# QUAD_BUCK.net
KiCad netlist of a schematic drawn in Altium Designer
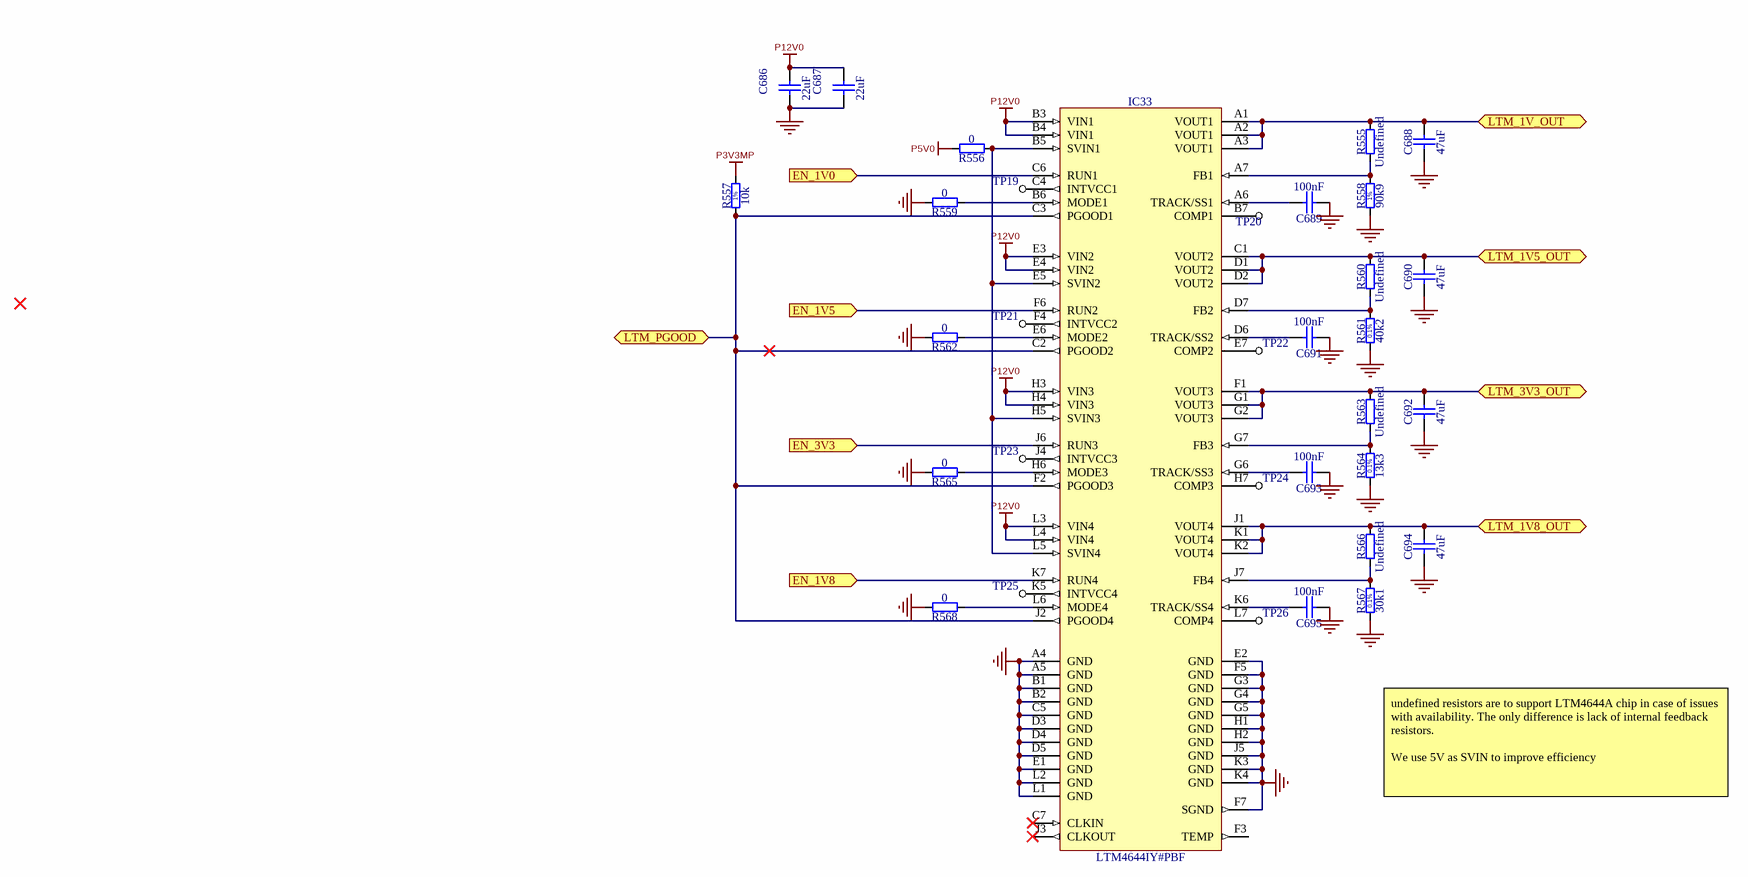
[diagram p0: QUAD_BUCK.SchDoc]

(export (version "E")
  (design (tool "Eeschema 10.0.6"))
  (components
    (comp (ref "C686")
      (value "22uF")
      (footprint "CAPC2012X135N")
      (description "Non-polarised capacitor")
      (fields
        (field (name "MANUFACTURER PART NUMBER") "CC0805_22UF_16V_10%_X5R")
        (field (name "MANUFACTURER") "GENERIC")
        (field (name "AUTHOR") "CERN DEM JLC")
      )
      (libsource (lib "Capacitors") (part "Capacitor - non polarized"))
    )
    (comp (ref "C687")
      (value "22uF")
      (footprint "CAPC2012X135N")
      (description "Non-polarised capacitor")
      (fields
        (field (name "MANUFACTURER PART NUMBER") "CC0805_22UF_16V_10%_X5R")
        (field (name "MANUFACTURER") "GENERIC")
        (field (name "AUTHOR") "CERN DEM JLC")
      )
      (libsource (lib "Capacitors") (part "Capacitor - non polarized"))
    )
    (comp (ref "C688")
      (value "47uF")
      (footprint "CAPC2012X140N")
      (description "Non-polarised capacitor")
      (fields
        (field (name "MANUFACTURER PART NUMBER") "CC0805_47UF_6.3V_20%_X5R")
        (field (name "MANUFACTURER") "GENERIC")
        (field (name "AUTHOR") "CERN DEM JLC")
      )
      (libsource (lib "Capacitors") (part "Capacitor - non polarized"))
    )
    (comp (ref "C689")
      (value "100nF")
      (footprint "CAPC1005X55N")
      (description "Non-polarised capacitor")
      (fields
        (field (name "PART NUMBER") "CC0402_100NF_16V_10%_X5R")
        (field (name "VOLTAGE") "16V")
        (field (name "AUTHOR") "CERN DEM JLC")
      )
      (libsource (lib "Capacitors") (part "Capacitor - non polarized"))
    )
    (comp (ref "C690")
      (value "47uF")
      (footprint "CAPC2012X140N")
      (description "Non-polarised capacitor")
      (fields
        (field (name "MANUFACTURER PART NUMBER") "CC0805_47UF_6.3V_20%_X5R")
        (field (name "MANUFACTURER") "GENERIC")
        (field (name "AUTHOR") "CERN DEM JLC")
      )
      (libsource (lib "Capacitors") (part "Capacitor - non polarized"))
    )
    (comp (ref "C691")
      (value "100nF")
      (footprint "CAPC1005X55N")
      (description "Non-polarised capacitor")
      (fields
        (field (name "PART NUMBER") "CC0402_100NF_16V_10%_X5R")
        (field (name "VOLTAGE") "16V")
        (field (name "AUTHOR") "CERN DEM JLC")
      )
      (libsource (lib "Capacitors") (part "Capacitor - non polarized"))
    )
    (comp (ref "C692")
      (value "47uF")
      (footprint "CAPC2012X140N")
      (description "Non-polarised capacitor")
      (fields
        (field (name "MANUFACTURER PART NUMBER") "CC0805_47UF_6.3V_20%_X5R")
        (field (name "MANUFACTURER") "GENERIC")
        (field (name "AUTHOR") "CERN DEM JLC")
      )
      (libsource (lib "Capacitors") (part "Capacitor - non polarized"))
    )
    (comp (ref "C693")
      (value "100nF")
      (footprint "CAPC1005X55N")
      (description "Non-polarised capacitor")
      (fields
        (field (name "PART NUMBER") "CC0402_100NF_16V_10%_X5R")
        (field (name "VOLTAGE") "16V")
        (field (name "AUTHOR") "CERN DEM JLC")
      )
      (libsource (lib "Capacitors") (part "Capacitor - non polarized"))
    )
    (comp (ref "C694")
      (value "47uF")
      (footprint "CAPC2012X140N")
      (description "Non-polarised capacitor")
      (fields
        (field (name "MANUFACTURER PART NUMBER") "CC0805_47UF_6.3V_20%_X5R")
        (field (name "MANUFACTURER") "GENERIC")
        (field (name "AUTHOR") "CERN DEM JLC")
      )
      (libsource (lib "Capacitors") (part "Capacitor - non polarized"))
    )
    (comp (ref "C695")
      (value "100nF")
      (footprint "CAPC1005X55N")
      (description "Non-polarised capacitor")
      (fields
        (field (name "PART NUMBER") "CC0402_100NF_16V_10%_X5R")
        (field (name "VOLTAGE") "16V")
        (field (name "AUTHOR") "CERN DEM JLC")
      )
      (libsource (lib "Capacitors") (part "Capacitor - non polarized"))
    )
    (comp (ref "IC33")
      (value "LTM4644IY#PBF")
      (footprint "BGA77C127P7X11_900X1500X521")
      (description "Quad DC/DC µModule Regulator with Configurable 4A Output Array")
      (fields (field (name "MANUFACTURER") "LINEAR TECHNOLOGY") (field (name "AUTHOR") "CERN DEM JLC"))
      (libsource (lib "ICs And Semiconductors") (part "LTM4644"))
    )
    (comp (ref "R555")
      (value "Undefined")
      (footprint "RESC1608X55N")
      (description "Resistor")
      (fields (field (name "PART NUMBER") "R0603_NO-VALUE") (field (name "AUTHOR") "CERN DEM JLC"))
      (libsource (lib "Resistors") (part "Resistor"))
    )
    (comp (ref "R556")
      (value "0")
      (footprint "RESC1005X40N")
      (description "Resistor")
      (fields
        (field (name "MANUFACTURER PART NUMBER") "R0402_0R_JUMPER")
        (field (name "MANUFACTURER") "GENERIC")
        (field (name "AUTHOR") "CERN DEM JLC")
      )
      (libsource (lib "Resistors") (part "Resistor"))
    )
    (comp (ref "R557")
      (value "10k")
      (footprint "RESC1005X40N")
      (description "Resistor - 1%")
      (fields
        (field (name "MANUFACTURER PART NUMBER") "R0402_10K_1%_0.0625W_100PPM")
        (field (name "MANUFACTURER") "GENERIC")
        (field (name "AUTHOR") "CERN DEM JLC")
      )
      (libsource (lib "Resistors") (part "Resistor - 1%"))
    )
    (comp (ref "R558")
      (value "90k9")
      (footprint "RESC1608X55N")
      (description "Resistor - 1%")
      (fields
        (field (name "PART NUMBER") "R0603_90K9_1%_0.1W_100PPM")
        (field (name "POWER") "0.1W")
        (field (name "AUTHOR") "CERN DEM JLC")
      )
      (libsource (lib "Resistors") (part "Resistor - 1%"))
    )
    (comp (ref "R559")
      (value "0")
      (footprint "RESC1005X40N")
      (description "Resistor")
      (fields
        (field (name "MANUFACTURER PART NUMBER") "R0402_0R_JUMPER")
        (field (name "MANUFACTURER") "GENERIC")
        (field (name "AUTHOR") "CERN DEM JLC")
      )
      (libsource (lib "Resistors") (part "Resistor"))
    )
    (comp (ref "R560")
      (value "Undefined")
      (footprint "RESC1608X55N")
      (description "Resistor")
      (fields (field (name "PART NUMBER") "R0603_NO-VALUE") (field (name "AUTHOR") "CERN DEM JLC"))
      (libsource (lib "Resistors") (part "Resistor"))
    )
    (comp (ref "R561")
      (value "40k2")
      (footprint "RESC1608X55N")
      (description "Resistor - 0.1%")
      (fields
        (field (name "PART NUMBER") "R0603_40K2_0.1%_0.063W_10PPM")
        (field (name "POWER") "0.063W")
        (field (name "AUTHOR") "CERN DEM JLC")
      )
      (libsource (lib "Resistors") (part "Resistor - 0.1%"))
    )
    (comp (ref "R562")
      (value "0")
      (footprint "RESC1005X40N")
      (description "Resistor")
      (fields
        (field (name "MANUFACTURER PART NUMBER") "R0402_0R_JUMPER")
        (field (name "MANUFACTURER") "GENERIC")
        (field (name "AUTHOR") "CERN DEM JLC")
      )
      (libsource (lib "Resistors") (part "Resistor"))
    )
    (comp (ref "R563")
      (value "Undefined")
      (footprint "RESC1608X55N")
      (description "Resistor")
      (fields (field (name "PART NUMBER") "R0603_NO-VALUE") (field (name "AUTHOR") "CERN DEM JLC"))
      (libsource (lib "Resistors") (part "Resistor"))
    )
    (comp (ref "R564")
      (value "13k3")
      (footprint "RESC1608X55N")
      (description "Resistor - 0.1%")
      (fields
        (field (name "PART NUMBER") "R0603_13K3_0.1%_0.063W_10PPM")
        (field (name "POWER") "0.063W")
        (field (name "AUTHOR") "CERN DEM JLC")
      )
      (libsource (lib "Resistors") (part "Resistor - 0.1%"))
    )
    (comp (ref "R565")
      (value "0")
      (footprint "RESC1005X40N")
      (description "Resistor")
      (fields
        (field (name "MANUFACTURER PART NUMBER") "R0402_0R_JUMPER")
        (field (name "MANUFACTURER") "GENERIC")
        (field (name "AUTHOR") "CERN DEM JLC")
      )
      (libsource (lib "Resistors") (part "Resistor"))
    )
    (comp (ref "R566")
      (value "Undefined")
      (footprint "RESC1608X55N")
      (description "Resistor")
      (fields (field (name "PART NUMBER") "R0603_NO-VALUE") (field (name "AUTHOR") "CERN DEM JLC"))
      (libsource (lib "Resistors") (part "Resistor"))
    )
    (comp (ref "R567")
      (value "30k1")
      (footprint "RESC1608X55N")
      (description "Resistor - 0.1%")
      (fields
        (field (name "PART NUMBER") "R0603_30K1_0.1%_0.063W_10PPM")
        (field (name "POWER") "0.063W")
        (field (name "AUTHOR") "CERN DEM JLC")
      )
      (libsource (lib "Resistors") (part "Resistor - 0.1%"))
    )
    (comp (ref "R568")
      (value "0")
      (footprint "RESC1005X40N")
      (description "Resistor")
      (fields
        (field (name "MANUFACTURER PART NUMBER") "R0402_0R_JUMPER")
        (field (name "MANUFACTURER") "GENERIC")
        (field (name "AUTHOR") "CERN DEM JLC")
      )
      (libsource (lib "Resistors") (part "Resistor"))
    )
    (comp (ref "TP19")
      (value "TP")
      (footprint "TP")
      (description "Testpoint")
      (libsource (lib "LIBRARY_SCH") (part "TP"))
    )
    (comp (ref "TP20")
      (value "TP")
      (footprint "TP")
      (description "Testpoint")
      (libsource (lib "LIBRARY_SCH") (part "TP"))
    )
    (comp (ref "TP21")
      (value "TP")
      (footprint "TP")
      (description "Testpoint")
      (libsource (lib "LIBRARY_SCH") (part "TP"))
    )
    (comp (ref "TP22")
      (value "TP")
      (footprint "TP")
      (description "Testpoint")
      (libsource (lib "LIBRARY_SCH") (part "TP"))
    )
    (comp (ref "TP23")
      (value "TP")
      (footprint "TP")
      (description "Testpoint")
      (libsource (lib "LIBRARY_SCH") (part "TP"))
    )
    (comp (ref "TP24")
      (value "TP")
      (footprint "TP")
      (description "Testpoint")
      (libsource (lib "LIBRARY_SCH") (part "TP"))
    )
    (comp (ref "TP25")
      (value "TP")
      (footprint "TP")
      (description "Testpoint")
      (libsource (lib "LIBRARY_SCH") (part "TP"))
    )
    (comp (ref "TP26")
      (value "TP")
      (footprint "TP")
      (description "Testpoint")
      (libsource (lib "LIBRARY_SCH") (part "TP"))
    )
  )
  (nets
    (net (code "1") (name "/EN_1V0") (class "Default")
      (node (ref "IC33") (pin "C6") (pinfunction "RUN1_C6") (pintype "input"))
    )
    (net (code "2") (name "/EN_1V5") (class "Default")
      (node (ref "IC33") (pin "F6") (pinfunction "RUN2_F6") (pintype "input"))
    )
    (net (code "3") (name "/EN_1V8") (class "Default")
      (node (ref "IC33") (pin "K7") (pinfunction "RUN4_K7") (pintype "input"))
    )
    (net (code "4") (name "/EN_3V3") (class "Default")
      (node (ref "IC33") (pin "J6") (pinfunction "RUN3_J6") (pintype "input"))
    )
    (net (code "5") (name "/LTM_1V5_OUT") (class "Default")
      (node (ref "C690") (pin "2") (pinfunction "2_2") (pintype "passive"))
      (node (ref "IC33") (pin "C1") (pinfunction "VOUT2_C1") (pintype "power_in"))
      (node (ref "IC33") (pin "D1") (pinfunction "VOUT2_D1") (pintype "power_in"))
      (node (ref "IC33") (pin "D2") (pinfunction "VOUT2_D2") (pintype "power_in"))
      (node (ref "R560") (pin "2") (pinfunction "2_2") (pintype "passive"))
    )
    (net (code "6") (name "/LTM_1V8_OUT") (class "Default")
      (node (ref "C694") (pin "2") (pinfunction "2_2") (pintype "passive"))
      (node (ref "IC33") (pin "J1") (pinfunction "VOUT4_J1") (pintype "power_in"))
      (node (ref "IC33") (pin "K1") (pinfunction "VOUT4_K1") (pintype "power_in"))
      (node (ref "IC33") (pin "K2") (pinfunction "VOUT4_K2") (pintype "power_in"))
      (node (ref "R566") (pin "2") (pinfunction "2_2") (pintype "passive"))
    )
    (net (code "7") (name "/LTM_1V_OUT") (class "Default")
      (node (ref "C688") (pin "2") (pinfunction "2_2") (pintype "passive"))
      (node (ref "IC33") (pin "A1") (pinfunction "VOUT1_A1") (pintype "power_in"))
      (node (ref "IC33") (pin "A2") (pinfunction "VOUT1_A2") (pintype "power_in"))
      (node (ref "IC33") (pin "A3") (pinfunction "VOUT1_A3") (pintype "power_in"))
      (node (ref "R555") (pin "2") (pinfunction "2_2") (pintype "passive"))
    )
    (net (code "8") (name "/LTM_3V3_OUT") (class "Default")
      (node (ref "C692") (pin "2") (pinfunction "2_2") (pintype "passive"))
      (node (ref "IC33") (pin "F1") (pinfunction "VOUT3_F1") (pintype "power_in"))
      (node (ref "IC33") (pin "G1") (pinfunction "VOUT3_G1") (pintype "power_in"))
      (node (ref "IC33") (pin "G2") (pinfunction "VOUT3_G2") (pintype "power_in"))
      (node (ref "R563") (pin "2") (pinfunction "2_2") (pintype "passive"))
    )
    (net (code "9") (name "/LTM_PGOOD") (class "Default")
      (node (ref "IC33") (pin "C2") (pinfunction "PGOOD2_C2") (pintype "output"))
      (node (ref "IC33") (pin "C3") (pinfunction "PGOOD1_C3") (pintype "output"))
      (node (ref "IC33") (pin "F2") (pinfunction "PGOOD3_F2") (pintype "output"))
      (node (ref "IC33") (pin "J2") (pinfunction "PGOOD4_J2") (pintype "output"))
      (node (ref "R557") (pin "1") (pinfunction "1_1") (pintype "passive"))
    )
    (net (code "10") (name "GND") (class "Default")
      (node (ref "C686") (pin "1") (pinfunction "1_1") (pintype "passive"))
      (node (ref "C687") (pin "1") (pinfunction "1_1") (pintype "passive"))
      (node (ref "C688") (pin "1") (pinfunction "1_1") (pintype "passive"))
      (node (ref "C689") (pin "1") (pinfunction "1_1") (pintype "passive"))
      (node (ref "C690") (pin "1") (pinfunction "1_1") (pintype "passive"))
      (node (ref "C691") (pin "1") (pinfunction "1_1") (pintype "passive"))
      (node (ref "C692") (pin "1") (pinfunction "1_1") (pintype "passive"))
      (node (ref "C693") (pin "1") (pinfunction "1_1") (pintype "passive"))
      (node (ref "C694") (pin "1") (pinfunction "1_1") (pintype "passive"))
      (node (ref "C695") (pin "1") (pinfunction "1_1") (pintype "passive"))
      (node (ref "IC33") (pin "A4") (pinfunction "GND_A4") (pintype "power_in"))
      (node (ref "IC33") (pin "A5") (pinfunction "GND_A5") (pintype "power_in"))
      (node (ref "IC33") (pin "B1") (pinfunction "GND_B1") (pintype "power_in"))
      (node (ref "IC33") (pin "B2") (pinfunction "GND_B2") (pintype "power_in"))
      (node (ref "IC33") (pin "C5") (pinfunction "GND_C5") (pintype "power_in"))
      (node (ref "IC33") (pin "D3") (pinfunction "GND_D3") (pintype "power_in"))
      (node (ref "IC33") (pin "D4") (pinfunction "GND_D4") (pintype "power_in"))
      (node (ref "IC33") (pin "D5") (pinfunction "GND_D5") (pintype "power_in"))
      (node (ref "IC33") (pin "E1") (pinfunction "GND_E1") (pintype "power_in"))
      (node (ref "IC33") (pin "E2") (pinfunction "GND_E2") (pintype "power_in"))
      (node (ref "IC33") (pin "F5") (pinfunction "GND_F5") (pintype "power_in"))
      (node (ref "IC33") (pin "F7") (pinfunction "SGND_F7") (pintype "output"))
      (node (ref "IC33") (pin "G3") (pinfunction "GND_G3") (pintype "power_in"))
      (node (ref "IC33") (pin "G4") (pinfunction "GND_G4") (pintype "power_in"))
      (node (ref "IC33") (pin "G5") (pinfunction "GND_G5") (pintype "power_in"))
      (node (ref "IC33") (pin "H1") (pinfunction "GND_H1") (pintype "power_in"))
      (node (ref "IC33") (pin "H2") (pinfunction "GND_H2") (pintype "power_in"))
      (node (ref "IC33") (pin "J5") (pinfunction "GND_J5") (pintype "power_in"))
      (node (ref "IC33") (pin "K3") (pinfunction "GND_K3") (pintype "power_in"))
      (node (ref "IC33") (pin "K4") (pinfunction "GND_K4") (pintype "power_in"))
      (node (ref "IC33") (pin "L1") (pinfunction "GND_L1") (pintype "power_in"))
      (node (ref "IC33") (pin "L2") (pinfunction "GND_L2") (pintype "power_in"))
      (node (ref "R558") (pin "1") (pinfunction "1_1") (pintype "passive"))
      (node (ref "R559") (pin "2") (pinfunction "2_2") (pintype "passive"))
      (node (ref "R561") (pin "1") (pinfunction "1_1") (pintype "passive"))
      (node (ref "R562") (pin "2") (pinfunction "2_2") (pintype "passive"))
      (node (ref "R564") (pin "1") (pinfunction "1_1") (pintype "passive"))
      (node (ref "R565") (pin "2") (pinfunction "2_2") (pintype "passive"))
      (node (ref "R567") (pin "1") (pinfunction "1_1") (pintype "passive"))
      (node (ref "R568") (pin "2") (pinfunction "2_2") (pintype "passive"))
    )
    (net (code "11") (name "Net-(IC33-COMP1)") (class "Default")
      (node (ref "IC33") (pin "B7") (pinfunction "COMP1_B7") (pintype "passive"))
      (node (ref "TP20") (pin "1") (pintype "passive"))
    )
    (net (code "12") (name "Net-(IC33-COMP2)") (class "Default")
      (node (ref "IC33") (pin "E7") (pinfunction "COMP2_E7") (pintype "passive"))
      (node (ref "TP22") (pin "1") (pintype "passive"))
    )
    (net (code "13") (name "Net-(IC33-COMP3)") (class "Default")
      (node (ref "IC33") (pin "H7") (pinfunction "COMP3_H7") (pintype "passive"))
      (node (ref "TP24") (pin "1") (pintype "passive"))
    )
    (net (code "14") (name "Net-(IC33-COMP4)") (class "Default")
      (node (ref "IC33") (pin "L7") (pinfunction "COMP4_L7") (pintype "passive"))
      (node (ref "TP26") (pin "1") (pintype "passive"))
    )
    (net (code "15") (name "Net-(IC33-FB1)") (class "Default")
      (node (ref "IC33") (pin "A7") (pinfunction "FB1_A7") (pintype "input"))
      (node (ref "R555") (pin "1") (pinfunction "1_1") (pintype "passive"))
      (node (ref "R558") (pin "2") (pinfunction "2_2") (pintype "passive"))
    )
    (net (code "16") (name "Net-(IC33-FB2)") (class "Default")
      (node (ref "IC33") (pin "D7") (pinfunction "FB2_D7") (pintype "input"))
      (node (ref "R560") (pin "1") (pinfunction "1_1") (pintype "passive"))
      (node (ref "R561") (pin "2") (pinfunction "2_2") (pintype "passive"))
    )
    (net (code "17") (name "Net-(IC33-FB3)") (class "Default")
      (node (ref "IC33") (pin "G7") (pinfunction "FB3_G7") (pintype "input"))
      (node (ref "R563") (pin "1") (pinfunction "1_1") (pintype "passive"))
      (node (ref "R564") (pin "2") (pinfunction "2_2") (pintype "passive"))
    )
    (net (code "18") (name "Net-(IC33-FB4)") (class "Default")
      (node (ref "IC33") (pin "J7") (pinfunction "FB4_J7") (pintype "input"))
      (node (ref "R566") (pin "1") (pinfunction "1_1") (pintype "passive"))
      (node (ref "R567") (pin "2") (pinfunction "2_2") (pintype "passive"))
    )
    (net (code "19") (name "Net-(IC33-INTVCC1)") (class "Default")
      (node (ref "IC33") (pin "C4") (pinfunction "INTVCC1_C4") (pintype "output"))
      (node (ref "TP19") (pin "1") (pintype "passive"))
    )
    (net (code "20") (name "Net-(IC33-INTVCC2)") (class "Default")
      (node (ref "IC33") (pin "F4") (pinfunction "INTVCC2_F4") (pintype "output"))
      (node (ref "TP21") (pin "1") (pintype "passive"))
    )
    (net (code "21") (name "Net-(IC33-INTVCC3)") (class "Default")
      (node (ref "IC33") (pin "J4") (pinfunction "INTVCC3_J4") (pintype "output"))
      (node (ref "TP23") (pin "1") (pintype "passive"))
    )
    (net (code "22") (name "Net-(IC33-INTVCC4)") (class "Default")
      (node (ref "IC33") (pin "K5") (pinfunction "INTVCC4_K5") (pintype "output"))
      (node (ref "TP25") (pin "1") (pintype "passive"))
    )
    (net (code "23") (name "Net-(IC33-MODE1)") (class "Default")
      (node (ref "IC33") (pin "B6") (pinfunction "MODE1_B6") (pintype "input"))
      (node (ref "R559") (pin "1") (pinfunction "1_1") (pintype "passive"))
    )
    (net (code "24") (name "Net-(IC33-MODE2)") (class "Default")
      (node (ref "IC33") (pin "E6") (pinfunction "MODE2_E6") (pintype "input"))
      (node (ref "R562") (pin "1") (pinfunction "1_1") (pintype "passive"))
    )
    (net (code "25") (name "Net-(IC33-MODE3)") (class "Default")
      (node (ref "IC33") (pin "H6") (pinfunction "MODE3_H6") (pintype "input"))
      (node (ref "R565") (pin "1") (pinfunction "1_1") (pintype "passive"))
    )
    (net (code "26") (name "Net-(IC33-MODE4)") (class "Default")
      (node (ref "IC33") (pin "L6") (pinfunction "MODE4_L6") (pintype "input"))
      (node (ref "R568") (pin "1") (pinfunction "1_1") (pintype "passive"))
    )
    (net (code "27") (name "Net-(IC33-SVIN1)") (class "Default")
      (node (ref "IC33") (pin "B5") (pinfunction "SVIN1_B5") (pintype "input"))
      (node (ref "IC33") (pin "E5") (pinfunction "SVIN2_E5") (pintype "input"))
      (node (ref "IC33") (pin "H5") (pinfunction "SVIN3_H5") (pintype "input"))
      (node (ref "IC33") (pin "L5") (pinfunction "SVIN4_L5") (pintype "input"))
      (node (ref "R556") (pin "1") (pinfunction "1_1") (pintype "passive"))
    )
    (net (code "28") (name "Net-(IC33-TRACK{slash}SS1)") (class "Default")
      (node (ref "C689") (pin "2") (pinfunction "2_2") (pintype "passive"))
      (node (ref "IC33") (pin "A6") (pinfunction "TRACK/SS1_A6") (pintype "input"))
    )
    (net (code "29") (name "Net-(IC33-TRACK{slash}SS2)") (class "Default")
      (node (ref "C691") (pin "2") (pinfunction "2_2") (pintype "passive"))
      (node (ref "IC33") (pin "D6") (pinfunction "TRACK/SS2_D6") (pintype "input"))
    )
    (net (code "30") (name "Net-(IC33-TRACK{slash}SS3)") (class "Default")
      (node (ref "C693") (pin "2") (pinfunction "2_2") (pintype "passive"))
      (node (ref "IC33") (pin "G6") (pinfunction "TRACK/SS3_G6") (pintype "input"))
    )
    (net (code "31") (name "Net-(IC33-TRACK{slash}SS4)") (class "Default")
      (node (ref "C695") (pin "2") (pinfunction "2_2") (pintype "passive"))
      (node (ref "IC33") (pin "K6") (pinfunction "TRACK/SS4_K6") (pintype "input"))
    )
    (net (code "32") (name "P3V3MP") (class "Default")
      (node (ref "R557") (pin "2") (pinfunction "2_2") (pintype "passive"))
    )
    (net (code "33") (name "P5V0") (class "Default")
      (node (ref "R556") (pin "2") (pinfunction "2_2") (pintype "passive"))
    )
    (net (code "34") (name "P12V0") (class "Default")
      (node (ref "C686") (pin "2") (pinfunction "2_2") (pintype "passive"))
      (node (ref "C687") (pin "2") (pinfunction "2_2") (pintype "passive"))
      (node (ref "IC33") (pin "B3") (pinfunction "VIN1_B3") (pintype "input"))
      (node (ref "IC33") (pin "B4") (pinfunction "VIN1_B4") (pintype "input"))
      (node (ref "IC33") (pin "E3") (pinfunction "VIN2_E3") (pintype "input"))
      (node (ref "IC33") (pin "E4") (pinfunction "VIN2_E4") (pintype "input"))
      (node (ref "IC33") (pin "H3") (pinfunction "VIN3_H3") (pintype "input"))
      (node (ref "IC33") (pin "H4") (pinfunction "VIN3_H4") (pintype "input"))
      (node (ref "IC33") (pin "L3") (pinfunction "VIN4_L3") (pintype "input"))
      (node (ref "IC33") (pin "L4") (pinfunction "VIN4_L4") (pintype "input"))
    )
    (net (code "35") (name "unconnected-(IC33-CLKIN-PadC7)") (class "Default")
      (node (ref "IC33") (pin "C7") (pinfunction "CLKIN_C7") (pintype "input+no_connect"))
    )
    (net (code "36") (name "unconnected-(IC33-CLKOUT-PadJ3)") (class "Default")
      (node (ref "IC33") (pin "J3") (pinfunction "CLKOUT_J3") (pintype "output+no_connect"))
    )
    (net (code "37") (name "unconnected-(IC33-TEMP-PadF3)") (class "Default")
      (node (ref "IC33") (pin "F3") (pinfunction "TEMP_F3") (pintype "output"))
    )
  )
)
